# 0007_h_field_probe_5mm.net
KiCad netlist of a schematic drawn in EAGLE
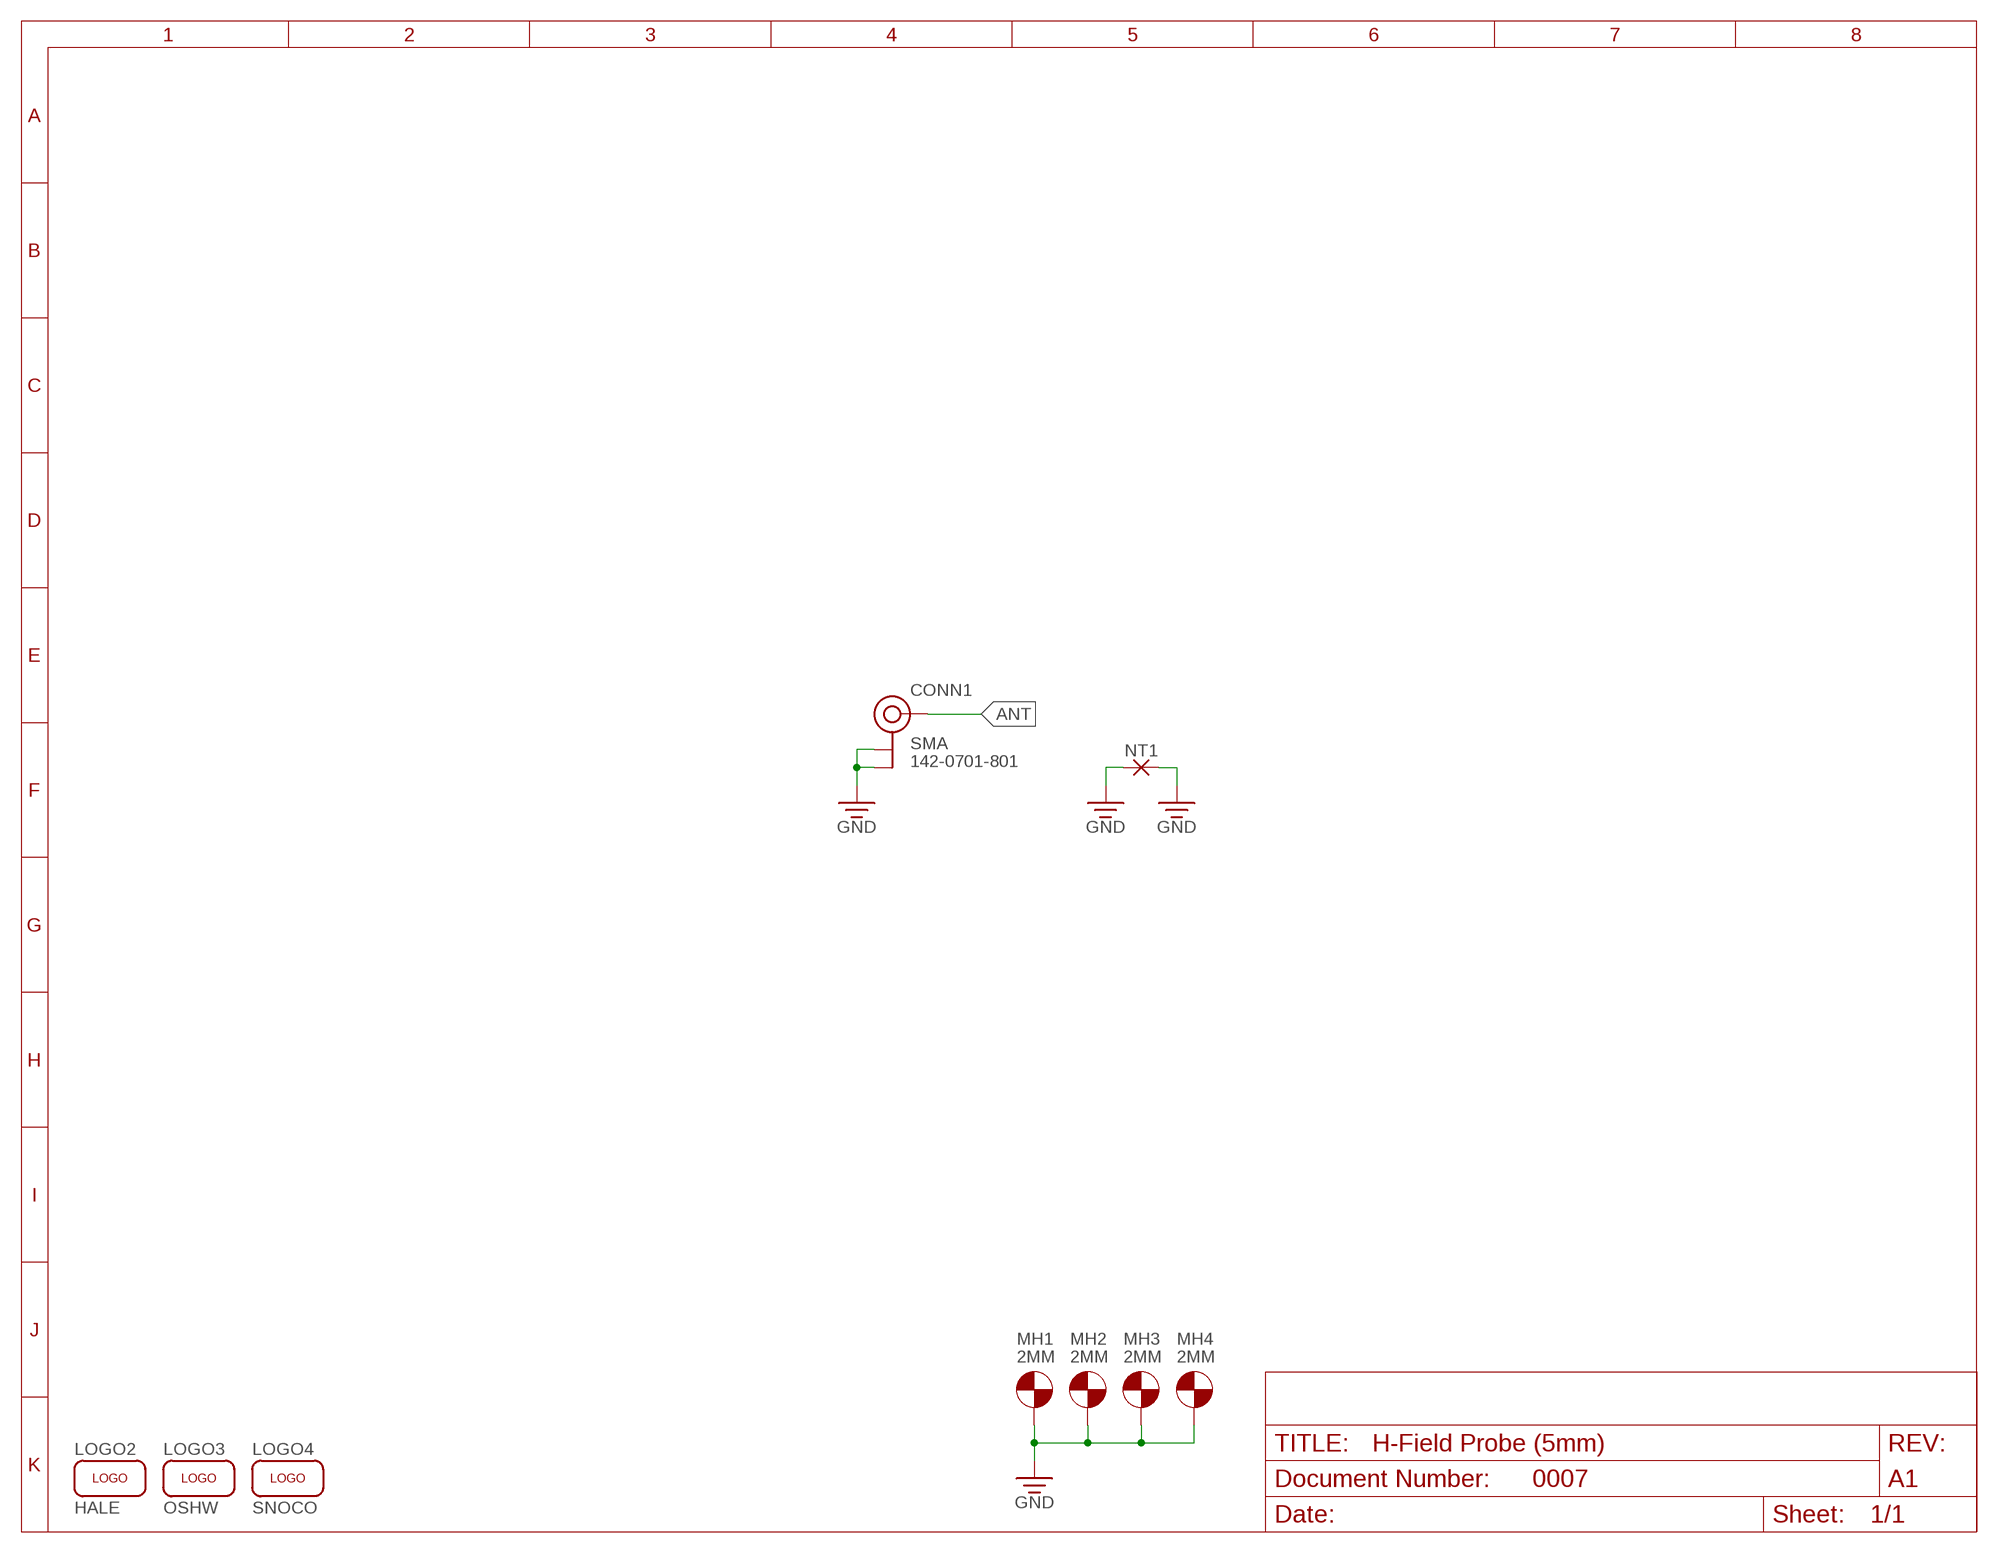
[diagram p0: schematic, sheet 1]

(export (version "E")
  (design (tool "Eeschema 10.0.6"))
  (components
    (comp (ref "CONN1")
      (value "SMA")
      (footprint "eagle-import:SMA-142-0701-801")
      (fields (field (name "MFG") "Cinch Connectivity Solutions Johnson"))
      (libsource (lib "eagle-import") (part "COAX-CONNECTOR-EDGE-SMA"))
    )
    (comp (ref "LOGO2")
      (value "HALE")
      (footprint "eagle-import:HALE-SILK-ICON")
      (libsource (lib "eagle-import") (part "LOGO-HALE"))
    )
    (comp (ref "LOGO3")
      (value "OSHW")
      (footprint "eagle-import:OSHW-SILK-ICON")
      (libsource (lib "eagle-import") (part "LOGO-OSHW"))
    )
    (comp (ref "LOGO4")
      (value "SNOCO")
      (footprint "eagle-import:SNOCO-SILK-ICON")
      (libsource (lib "eagle-import") (part "LOGO-SNOCO"))
    )
    (comp (ref "MH1")
      (value "2MM")
      (footprint "eagle-import:MH-M2-ELEC")
      (libsource (lib "eagle-import") (part "MH-ELEC-M2"))
    )
    (comp (ref "MH2")
      (value "2MM")
      (footprint "eagle-import:MH-M2-ELEC")
      (libsource (lib "eagle-import") (part "MH-ELEC-M2"))
    )
    (comp (ref "MH3")
      (value "2MM")
      (footprint "eagle-import:MH-M2-ELEC")
      (libsource (lib "eagle-import") (part "MH-ELEC-M2"))
    )
    (comp (ref "MH4")
      (value "2MM")
      (footprint "eagle-import:MH-M2-ELEC")
      (libsource (lib "eagle-import") (part "MH-ELEC-M2"))
    )
    (comp (ref "NT1")
      (value "NETTIE-VIA-TB")
      (footprint "eagle-import:NETTIE-VIA-TB")
      (libsource (lib "eagle-import") (part "NETTIE-VIA-TB"))
    )
    (comp (ref "U$2")
      (value "FRAME-8.5X11-LANDSCAPE-LET")
      (footprint "eagle-import:FRAME-8.5X11-LANDSCAPE")
      (fields (field (name "DOCNUM") "0007") (field (name "TITLE") "H-Field Probe (5mm)"))
      (libsource (lib "eagle-import") (part "FRAME-8.5X11-LANDSCAPE-LET"))
    )
  )
  (nets
    (net (code "1") (name "ANT") (class "Default")
      (node (ref "CONN1") (pin "2") (pinfunction "SIGNAL_2") (pintype "passive"))
    )
    (net (code "2") (name "GND") (class "Default")
      (node (ref "CONN1") (pin "1") (pinfunction "GND_1") (pintype "power_in"))
      (node (ref "CONN1") (pin "3") (pinfunction "GND_3") (pintype "power_in"))
      (node (ref "CONN1") (pin "4") (pinfunction "GND_4") (pintype "power_in"))
      (node (ref "CONN1") (pin "5") (pinfunction "GND_5") (pintype "power_in"))
      (node (ref "MH1") (pin "1") (pinfunction "1_1") (pintype "passive"))
      (node (ref "MH2") (pin "1") (pinfunction "1_1") (pintype "passive"))
      (node (ref "MH3") (pin "1") (pinfunction "1_1") (pintype "passive"))
      (node (ref "MH4") (pin "1") (pinfunction "1_1") (pintype "passive"))
      (node (ref "NT1") (pin "1") (pinfunction "1_1") (pintype "passive"))
      (node (ref "NT1") (pin "2") (pinfunction "2_2") (pintype "passive"))
    )
  )
)
